# robo_shield.net
KiCad netlist of a schematic drawn in EAGLE
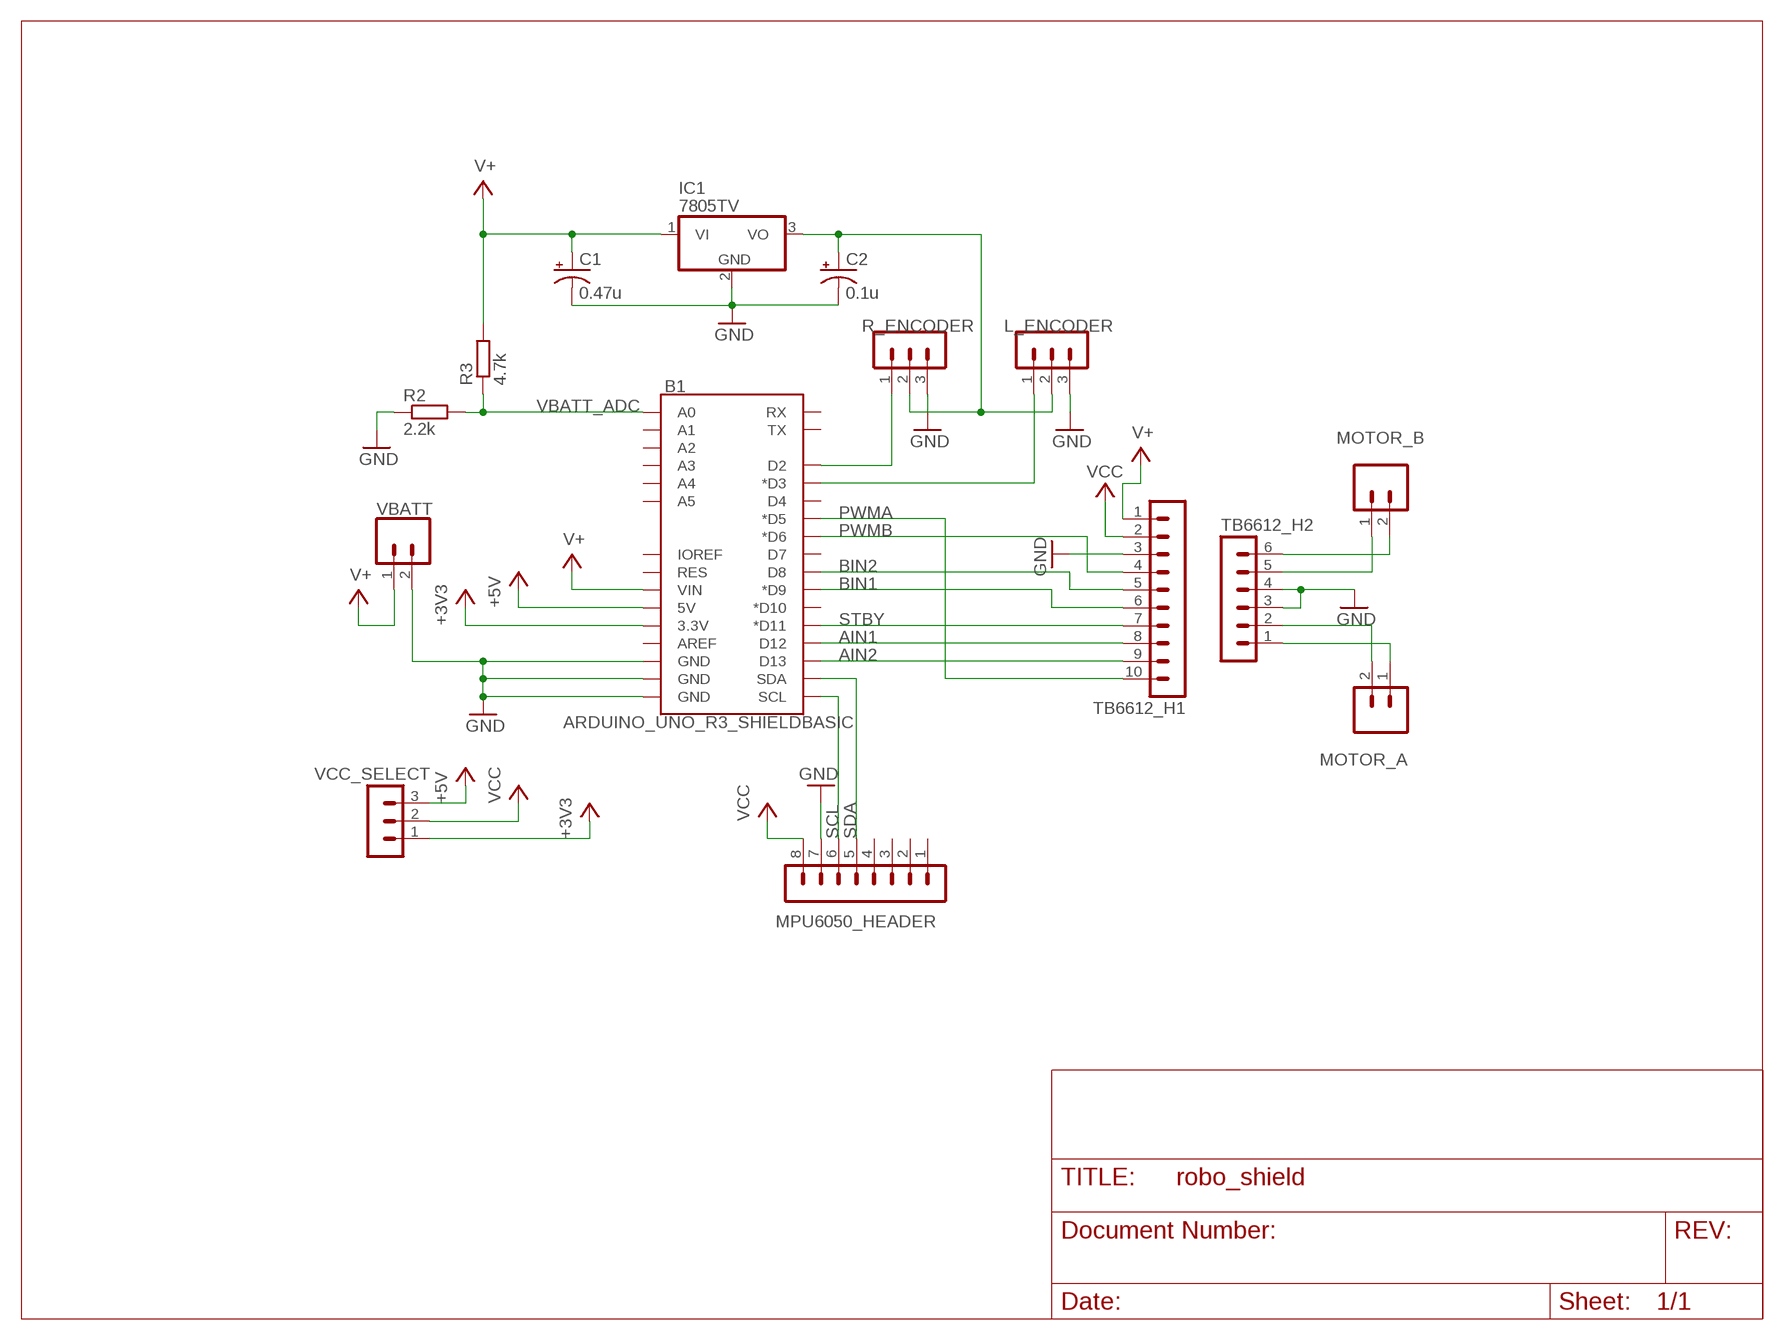
[diagram p0: schematic, sheet 1]

(export (version "E")
  (design (tool "Eeschema 10.0.6"))
  (components
    (comp (ref "B1")
      (value "ARDUINO_UNO_R3_SHIELDBASIC")
      (footprint "eagle-import:UNO_R3_SHIELD")
      (libsource (lib "eagle-import") (part "ARDUINO_UNO_R3_SHIELDBASIC"))
    )
    (comp (ref "C1")
      (value "0.47u")
      (footprint "eagle-import:E5-5")
      (libsource (lib "eagle-import") (part "CPOL-USE5-5"))
    )
    (comp (ref "C2")
      (value "0.1u")
      (footprint "eagle-import:E5-5")
      (libsource (lib "eagle-import") (part "CPOL-USE5-5"))
    )
    (comp (ref "IC1")
      (value "7805TV")
      (footprint "eagle-import:TO220V")
      (libsource (lib "eagle-import") (part "78TV05"))
    )
    (comp (ref "L_ENCODER")
      (value "MA03-1")
      (footprint "eagle-import:MA03-1")
      (libsource (lib "eagle-import") (part "MA03-1"))
    )
    (comp (ref "MOTOR_A")
      (value "CONN_025MM")
      (footprint "eagle-import:SCREWTERMINAL-5MM-2")
      (libsource (lib "eagle-import") (part "CONN_025MM"))
    )
    (comp (ref "MOTOR_B")
      (value "CONN_025MM")
      (footprint "eagle-import:SCREWTERMINAL-5MM-2")
      (libsource (lib "eagle-import") (part "CONN_025MM"))
    )
    (comp (ref "MPU6050_HEADER")
      (value "MA08-1")
      (footprint "eagle-import:MA08-1")
      (libsource (lib "eagle-import") (part "MA08-1"))
    )
    (comp (ref "R2")
      (value "2.2k")
      (footprint "eagle-import:0207_10")
      (libsource (lib "eagle-import") (part "R-EU_0207/10"))
    )
    (comp (ref "R3")
      (value "4.7k")
      (footprint "eagle-import:0207_10")
      (libsource (lib "eagle-import") (part "R-EU_0207/10"))
    )
    (comp (ref "R_ENCODER")
      (value "MA03-1")
      (footprint "eagle-import:MA03-1")
      (libsource (lib "eagle-import") (part "MA03-1"))
    )
    (comp (ref "TB6612_H1")
      (value "MA10-1")
      (footprint "eagle-import:MA10-1")
      (libsource (lib "eagle-import") (part "MA10-1"))
    )
    (comp (ref "TB6612_H2")
      (value "MA06-1")
      (footprint "eagle-import:MA06-1")
      (libsource (lib "eagle-import") (part "MA06-1"))
    )
    (comp (ref "VBATT")
      (value "CONN_025MM")
      (footprint "eagle-import:SCREWTERMINAL-5MM-2")
      (libsource (lib "eagle-import") (part "CONN_025MM"))
    )
    (comp (ref "VCC_SELECT")
      (value "MA03-1")
      (footprint "eagle-import:MA03-1")
      (libsource (lib "eagle-import") (part "MA03-1"))
    )
  )
  (nets
    (net (code "1") (name "+3V3") (class "Default")
      (node (ref "B1") (pin "3.3V") (pinfunction "3.3V_3.3V") (pintype "bidirectional"))
      (node (ref "VCC_SELECT") (pin "1") (pinfunction "1_1") (pintype "passive"))
    )
    (net (code "2") (name "+5V") (class "Default")
      (node (ref "B1") (pin "5V") (pinfunction "5V_5V") (pintype "bidirectional"))
      (node (ref "VCC_SELECT") (pin "3") (pinfunction "3_3") (pintype "passive"))
    )
    (net (code "3") (name "/AIN1") (class "Default")
      (node (ref "B1") (pin "D12") (pinfunction "D12_D12") (pintype "bidirectional"))
      (node (ref "TB6612_H1") (pin "8") (pinfunction "8_8") (pintype "passive"))
    )
    (net (code "4") (name "/AIN2") (class "Default")
      (node (ref "B1") (pin "D13") (pinfunction "D13_D13") (pintype "bidirectional"))
      (node (ref "TB6612_H1") (pin "9") (pinfunction "9_9") (pintype "passive"))
    )
    (net (code "5") (name "/BIN1") (class "Default")
      (node (ref "B1") (pin "D9") (pinfunction "*D9_D9") (pintype "bidirectional"))
      (node (ref "TB6612_H1") (pin "6") (pinfunction "6_6") (pintype "passive"))
    )
    (net (code "6") (name "/BIN2") (class "Default")
      (node (ref "B1") (pin "D8") (pinfunction "D8_D8") (pintype "bidirectional"))
      (node (ref "TB6612_H1") (pin "5") (pinfunction "5_5") (pintype "passive"))
    )
    (net (code "7") (name "/PWMA") (class "Default")
      (node (ref "B1") (pin "D5") (pinfunction "*D5_D5") (pintype "bidirectional"))
      (node (ref "TB6612_H1") (pin "10") (pinfunction "10_10") (pintype "passive"))
    )
    (net (code "8") (name "/PWMB") (class "Default")
      (node (ref "B1") (pin "D6") (pinfunction "*D6_D6") (pintype "bidirectional"))
      (node (ref "TB6612_H1") (pin "4") (pinfunction "4_4") (pintype "passive"))
    )
    (net (code "9") (name "/SCL") (class "Default")
      (node (ref "B1") (pin "SCL") (pinfunction "SCL_SCL") (pintype "bidirectional"))
      (node (ref "MPU6050_HEADER") (pin "6") (pinfunction "6_6") (pintype "passive"))
    )
    (net (code "10") (name "/SDA") (class "Default")
      (node (ref "B1") (pin "SDA") (pinfunction "SDA_SDA") (pintype "bidirectional"))
      (node (ref "MPU6050_HEADER") (pin "5") (pinfunction "5_5") (pintype "passive"))
    )
    (net (code "11") (name "/STBY") (class "Default")
      (node (ref "B1") (pin "D11") (pinfunction "*D11_D11") (pintype "bidirectional"))
      (node (ref "TB6612_H1") (pin "7") (pinfunction "7_7") (pintype "passive"))
    )
    (net (code "12") (name "/VBATT_ADC") (class "Default")
      (node (ref "B1") (pin "A0") (pinfunction "A0_A0") (pintype "bidirectional"))
      (node (ref "R2") (pin "2") (pinfunction "2_2") (pintype "passive"))
      (node (ref "R3") (pin "1") (pinfunction "1_1") (pintype "passive"))
    )
    (net (code "13") (name "GND") (class "Default")
      (node (ref "B1") (pin "GND@0") (pinfunction "GND_GND@0") (pintype "bidirectional"))
      (node (ref "B1") (pin "GND@1") (pinfunction "GND_GND@1") (pintype "bidirectional"))
      (node (ref "B1") (pin "GND@2") (pinfunction "GND_GND@2") (pintype "bidirectional"))
      (node (ref "C1") (pin "-") (pinfunction "-_-") (pintype "passive"))
      (node (ref "C2") (pin "-") (pinfunction "-_-") (pintype "passive"))
      (node (ref "IC1") (pin "2") (pinfunction "GND_2") (pintype "passive"))
      (node (ref "L_ENCODER") (pin "3") (pinfunction "3_3") (pintype "passive"))
      (node (ref "MPU6050_HEADER") (pin "7") (pinfunction "7_7") (pintype "passive"))
      (node (ref "R2") (pin "1") (pinfunction "1_1") (pintype "passive"))
      (node (ref "R_ENCODER") (pin "3") (pinfunction "3_3") (pintype "passive"))
      (node (ref "TB6612_H1") (pin "3") (pinfunction "3_3") (pintype "passive"))
      (node (ref "TB6612_H2") (pin "3") (pinfunction "3_3") (pintype "passive"))
      (node (ref "TB6612_H2") (pin "4") (pinfunction "4_4") (pintype "passive"))
      (node (ref "VBATT") (pin "2") (pinfunction "2_2") (pintype "passive"))
    )
    (net (code "14") (name "Net-(B1-*D3)") (class "Default")
      (node (ref "B1") (pin "D3") (pinfunction "*D3_D3") (pintype "bidirectional"))
      (node (ref "L_ENCODER") (pin "1") (pinfunction "1_1") (pintype "passive"))
    )
    (net (code "15") (name "Net-(B1-PadD2)") (class "Default")
      (node (ref "B1") (pin "D2") (pinfunction "D2_D2") (pintype "bidirectional"))
      (node (ref "R_ENCODER") (pin "1") (pinfunction "1_1") (pintype "passive"))
    )
    (net (code "16") (name "Net-(IC1-VO)") (class "Default")
      (node (ref "C2") (pin "+") (pinfunction "+_+") (pintype "passive"))
      (node (ref "IC1") (pin "3") (pinfunction "VO_3") (pintype "passive"))
      (node (ref "L_ENCODER") (pin "2") (pinfunction "2_2") (pintype "passive"))
      (node (ref "R_ENCODER") (pin "2") (pinfunction "2_2") (pintype "passive"))
    )
    (net (code "17") (name "Net-(MOTOR_A-Pad1)") (class "Default")
      (node (ref "MOTOR_A") (pin "1") (pinfunction "1_1") (pintype "passive"))
      (node (ref "TB6612_H2") (pin "1") (pinfunction "1_1") (pintype "passive"))
    )
    (net (code "18") (name "Net-(MOTOR_A-Pad2)") (class "Default")
      (node (ref "MOTOR_A") (pin "2") (pinfunction "2_2") (pintype "passive"))
      (node (ref "TB6612_H2") (pin "2") (pinfunction "2_2") (pintype "passive"))
    )
    (net (code "19") (name "Net-(MOTOR_B-Pad1)") (class "Default")
      (node (ref "MOTOR_B") (pin "1") (pinfunction "1_1") (pintype "passive"))
      (node (ref "TB6612_H2") (pin "5") (pinfunction "5_5") (pintype "passive"))
    )
    (net (code "20") (name "Net-(MOTOR_B-Pad2)") (class "Default")
      (node (ref "MOTOR_B") (pin "2") (pinfunction "2_2") (pintype "passive"))
      (node (ref "TB6612_H2") (pin "6") (pinfunction "6_6") (pintype "passive"))
    )
    (net (code "21") (name "V+") (class "Default")
      (node (ref "B1") (pin "VIN") (pinfunction "VIN_VIN") (pintype "bidirectional"))
      (node (ref "C1") (pin "+") (pinfunction "+_+") (pintype "passive"))
      (node (ref "IC1") (pin "1") (pinfunction "VI_1") (pintype "input"))
      (node (ref "R3") (pin "2") (pinfunction "2_2") (pintype "passive"))
      (node (ref "TB6612_H1") (pin "1") (pinfunction "1_1") (pintype "passive"))
      (node (ref "VBATT") (pin "1") (pinfunction "1_1") (pintype "passive"))
    )
    (net (code "22") (name "VCC") (class "Default")
      (node (ref "MPU6050_HEADER") (pin "8") (pinfunction "8_8") (pintype "passive"))
      (node (ref "TB6612_H1") (pin "2") (pinfunction "2_2") (pintype "passive"))
      (node (ref "VCC_SELECT") (pin "2") (pinfunction "2_2") (pintype "passive"))
    )
    (net (code "23") (name "unconnected-(B1-*D10-PadD10)") (class "Default")
      (node (ref "B1") (pin "D10") (pinfunction "*D10_D10") (pintype "bidirectional"))
    )
    (net (code "24") (name "unconnected-(B1-PadA1)") (class "Default")
      (node (ref "B1") (pin "A1") (pinfunction "A1_A1") (pintype "bidirectional"))
    )
    (net (code "25") (name "unconnected-(B1-PadA2)") (class "Default")
      (node (ref "B1") (pin "A2") (pinfunction "A2_A2") (pintype "bidirectional"))
    )
    (net (code "26") (name "unconnected-(B1-PadA3)") (class "Default")
      (node (ref "B1") (pin "A3") (pinfunction "A3_A3") (pintype "bidirectional"))
    )
    (net (code "27") (name "unconnected-(B1-PadA4)") (class "Default")
      (node (ref "B1") (pin "A4") (pinfunction "A4_A4") (pintype "bidirectional"))
    )
    (net (code "28") (name "unconnected-(B1-PadA5)") (class "Default")
      (node (ref "B1") (pin "A5") (pinfunction "A5_A5") (pintype "bidirectional"))
    )
    (net (code "29") (name "unconnected-(B1-PadAREF)") (class "Default")
      (node (ref "B1") (pin "AREF") (pinfunction "AREF_AREF") (pintype "bidirectional"))
    )
    (net (code "30") (name "unconnected-(B1-PadD4)") (class "Default")
      (node (ref "B1") (pin "D4") (pinfunction "D4_D4") (pintype "bidirectional"))
    )
    (net (code "31") (name "unconnected-(B1-PadD7)") (class "Default")
      (node (ref "B1") (pin "D7") (pinfunction "D7_D7") (pintype "bidirectional"))
    )
    (net (code "32") (name "unconnected-(B1-PadIOREF)") (class "Default")
      (node (ref "B1") (pin "IOREF") (pinfunction "IOREF_IOREF") (pintype "bidirectional"))
    )
    (net (code "33") (name "unconnected-(B1-PadRES)") (class "Default")
      (node (ref "B1") (pin "RES") (pinfunction "RES_RES") (pintype "bidirectional"))
    )
    (net (code "34") (name "unconnected-(B1-PadRX)") (class "Default")
      (node (ref "B1") (pin "RX") (pinfunction "RX_RX") (pintype "bidirectional"))
    )
    (net (code "35") (name "unconnected-(B1-PadTX)") (class "Default")
      (node (ref "B1") (pin "TX") (pinfunction "TX_TX") (pintype "bidirectional"))
    )
    (net (code "36") (name "unconnected-(MPU6050_HEADER-Pad1)") (class "Default")
      (node (ref "MPU6050_HEADER") (pin "1") (pinfunction "1_1") (pintype "passive"))
    )
    (net (code "37") (name "unconnected-(MPU6050_HEADER-Pad2)") (class "Default")
      (node (ref "MPU6050_HEADER") (pin "2") (pinfunction "2_2") (pintype "passive"))
    )
    (net (code "38") (name "unconnected-(MPU6050_HEADER-Pad3)") (class "Default")
      (node (ref "MPU6050_HEADER") (pin "3") (pinfunction "3_3") (pintype "passive"))
    )
    (net (code "39") (name "unconnected-(MPU6050_HEADER-Pad4)") (class "Default")
      (node (ref "MPU6050_HEADER") (pin "4") (pinfunction "4_4") (pintype "passive"))
    )
  )
)
